# Sheet.net
KiCad netlist of a schematic drawn in Altium Designer
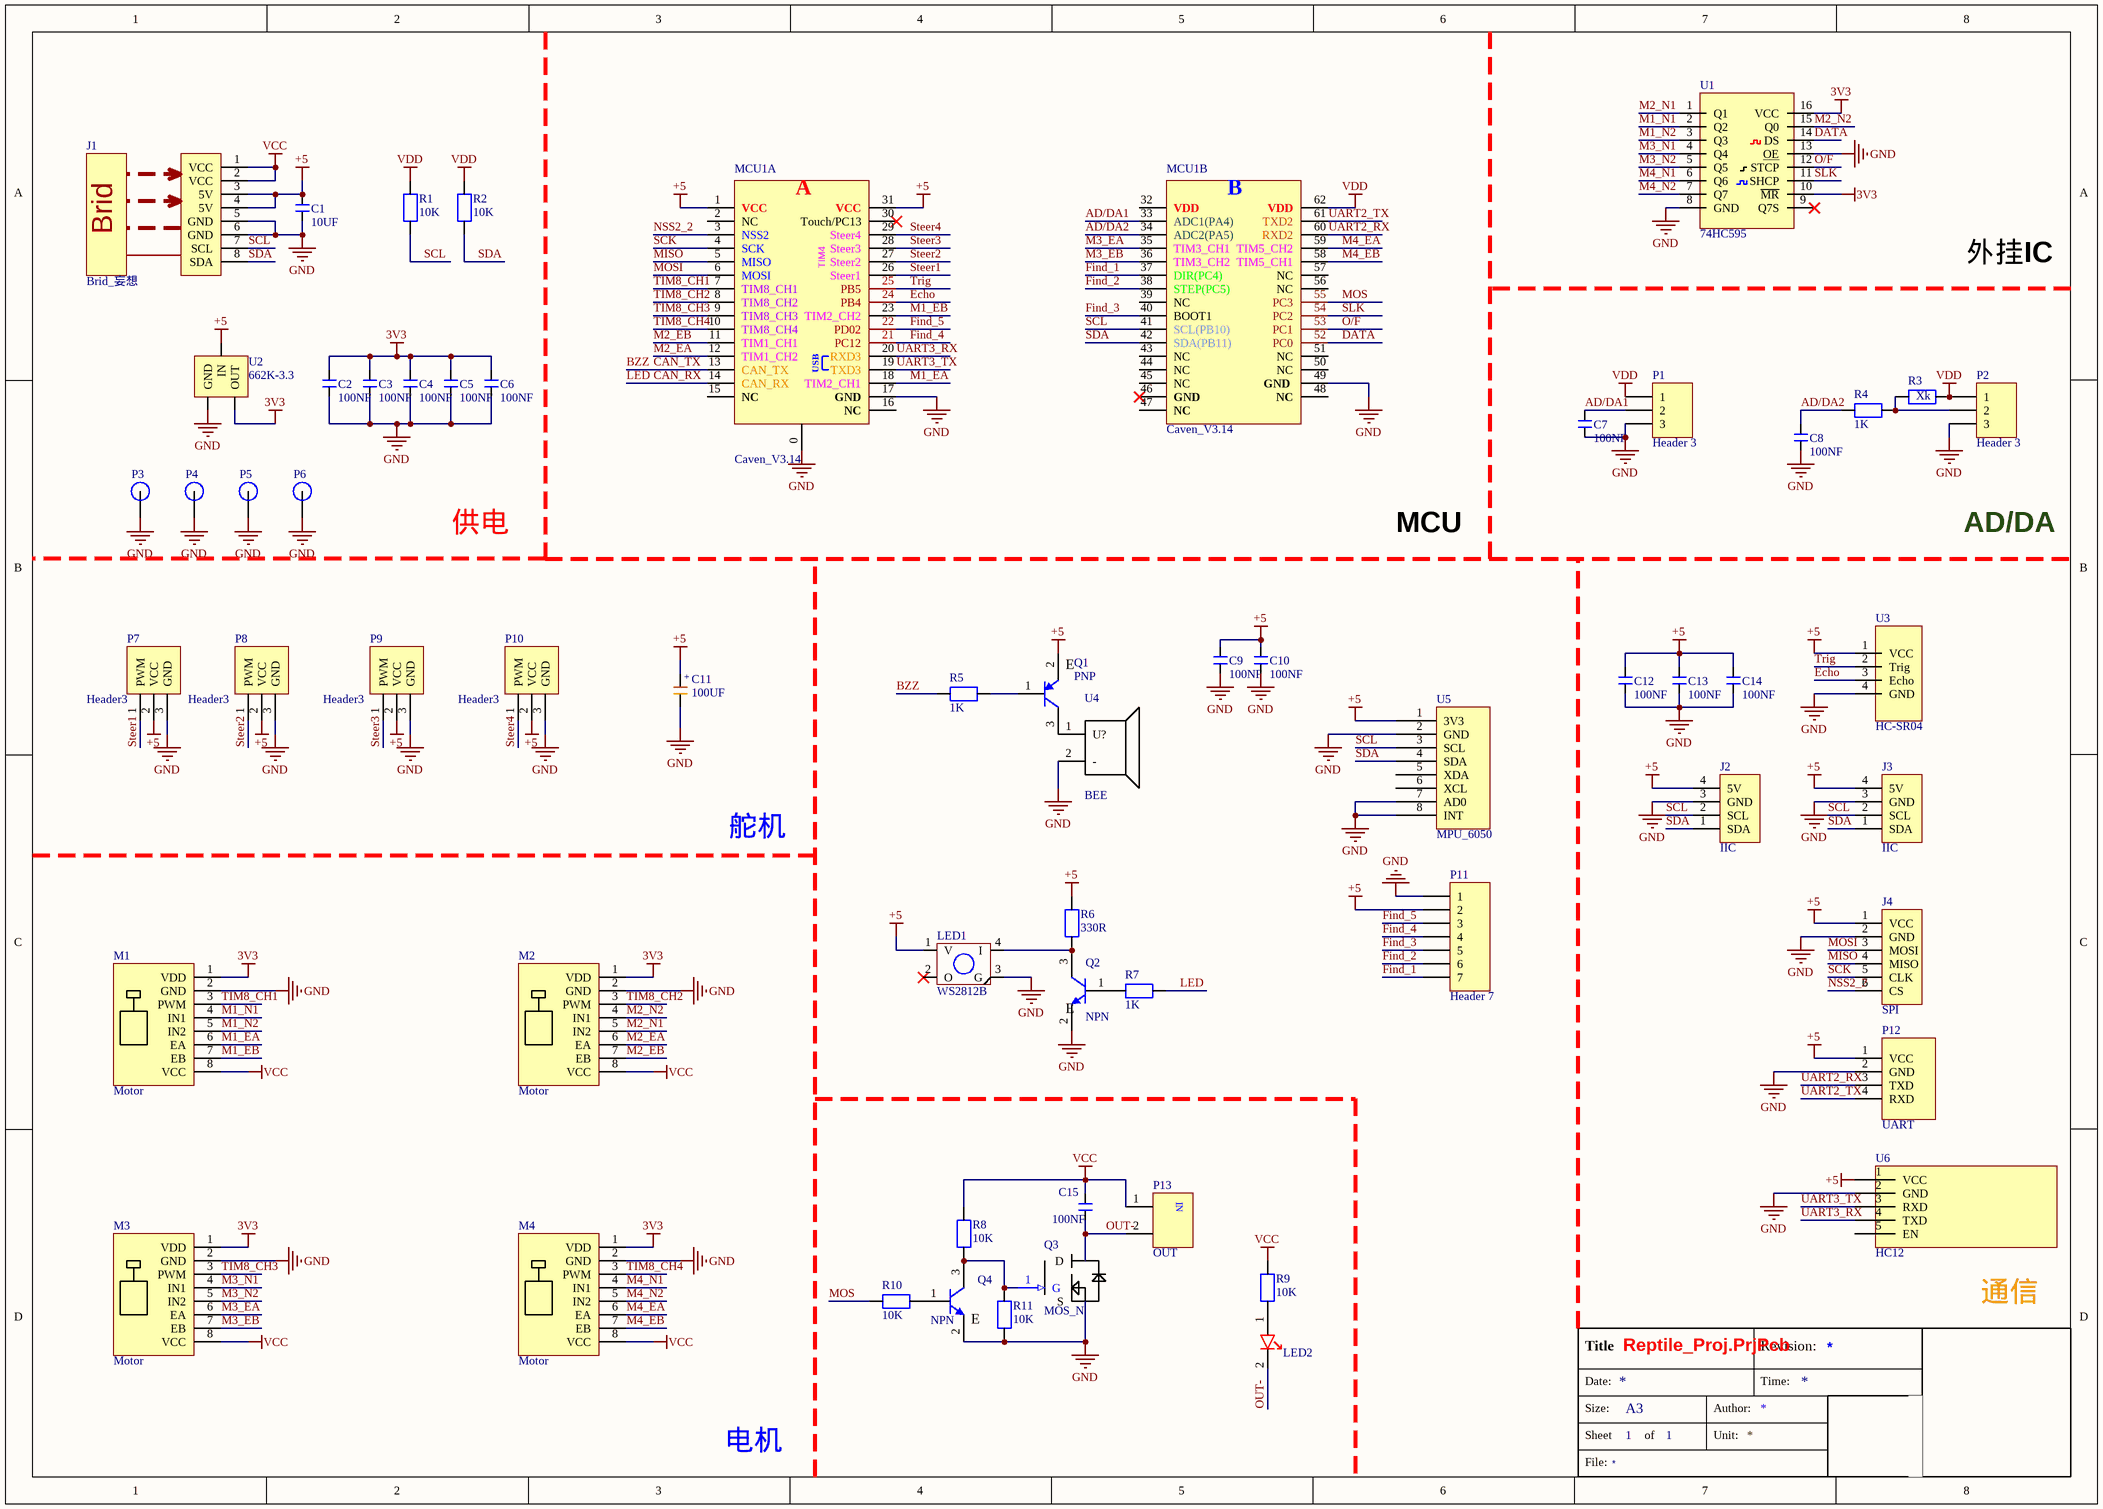
[diagram p0: Sheet.SchDoc]

(export (version "E")
  (design (tool "Eeschema 10.0.6"))
  (components
    (comp (ref "C1")
      (value "10UF")
      (footprint "CAP_1206")
      (description "CAP  12~50V")
      (libsource (lib "User") (part "CAP"))
    )
    (comp (ref "C2")
      (value "100NF")
      (footprint "CAP_0603")
      (description "CAP  12~50V")
      (libsource (lib "User") (part "CAP"))
    )
    (comp (ref "C3")
      (value "100NF")
      (footprint "CAP_0603")
      (description "CAP  12~50V")
      (libsource (lib "User") (part "CAP"))
    )
    (comp (ref "C4")
      (value "100NF")
      (footprint "CAP_0603")
      (description "CAP  12~50V")
      (libsource (lib "User") (part "CAP"))
    )
    (comp (ref "C5")
      (value "100NF")
      (footprint "CAP_0603")
      (description "CAP  12~50V")
      (libsource (lib "User") (part "CAP"))
    )
    (comp (ref "C6")
      (value "100NF")
      (footprint "CAP_0603")
      (description "CAP  12~50V")
      (libsource (lib "User") (part "CAP"))
    )
    (comp (ref "C7")
      (value "100NF")
      (footprint "CAP_0603")
      (description "CAP  12~50V")
      (libsource (lib "User") (part "CAP"))
    )
    (comp (ref "C8")
      (value "100NF")
      (footprint "CAP_0603")
      (description "CAP  12~50V")
      (libsource (lib "User") (part "CAP"))
    )
    (comp (ref "C9")
      (value "100NF")
      (footprint "CAP_0603")
      (description "CAP  12~50V")
      (libsource (lib "User") (part "CAP"))
    )
    (comp (ref "C10")
      (value "100NF")
      (footprint "CAP_0603")
      (description "CAP  12~50V")
      (libsource (lib "User") (part "CAP"))
    )
    (comp (ref "C11")
      (value "100UF")
      (footprint "CAP_3528_B")
      (description "CAP  6~12V  钽电容")
      (libsource (lib "User") (part "CAP_TA"))
    )
    (comp (ref "C12")
      (value "100NF")
      (footprint "CAP_0603")
      (description "CAP  12~50V")
      (libsource (lib "User") (part "CAP"))
    )
    (comp (ref "C13")
      (value "100NF")
      (footprint "CAP_0603")
      (description "CAP  12~50V")
      (libsource (lib "User") (part "CAP"))
    )
    (comp (ref "C14")
      (value "100NF")
      (footprint "CAP_0603")
      (description "CAP  12~50V")
      (libsource (lib "User") (part "CAP"))
    )
    (comp (ref "C15")
      (value "100NF")
      (footprint "CAP_0603")
      (description "CAP  12~50V")
      (libsource (lib "User") (part "CAP"))
    )
    (comp (ref "J1")
      (value "Brid_妄想")
      (footprint "Brid")
      (description "Brid")
      (libsource (lib "User") (part "Brid"))
    )
    (comp (ref "J2")
      (value "IIC")
      (footprint "XH_2.54_4P")
      (description "Heard")
      (libsource (lib "User") (part "IIC"))
    )
    (comp (ref "J3")
      (value "IIC")
      (footprint "IIC-XH2.54-4PIN")
      (description "Heard")
      (libsource (lib "User") (part "IIC"))
    )
    (comp (ref "J4")
      (value "SPI")
      (footprint "Header 2.54X6")
      (description "Heard")
      (libsource (lib "User") (part "SPI"))
    )
    (comp (ref "LED1")
      (value "WS2812B")
      (footprint "5050-RGB")
      (description "LED")
      (libsource (lib "User") (part "WS2812B"))
    )
    (comp (ref "LED2")
      (value "LED_R/G/B/Y")
      (footprint "LED_5MM")
      (description "LED")
      (libsource (lib "User") (part "LED"))
    )
    (comp (ref "M1")
      (value "Motor")
      (footprint "PH_2.0_8P")
      (description "Motor-Brushed-port,XH-1.25mm")
      (libsource (lib "User") (part "Motor-Brushed-port"))
    )
    (comp (ref "M2")
      (value "Motor")
      (footprint "PH_2.0_8P")
      (description "Motor-Brushed-port,XH-1.25mm")
      (libsource (lib "User") (part "Motor-Brushed-port"))
    )
    (comp (ref "M3")
      (value "Motor")
      (footprint "PH_2.0_8P")
      (description "Motor-Brushed-port,XH-1.25mm")
      (libsource (lib "User") (part "Motor-Brushed-port"))
    )
    (comp (ref "M4")
      (value "Motor")
      (footprint "PH_2.0_8P")
      (description "Motor-Brushed-port,XH-1.25mm")
      (libsource (lib "User") (part "Motor-Brushed-port"))
    )
    (comp (ref "MCU1")
      (value "Caven_V3.14")
      (footprint "Caven_3.14")
      (description "MCU_STM32F103RE")
      (libsource (lib "User") (part "Caven_V3.14"))
    )
    (comp (ref "P1")
      (value "Header 3")
      (footprint "Header 2.54X3")
      (description "Header, 3-Pin")
      (fields (field (name "PUBLISHER") "Altium Limited"))
      (libsource (lib "Miscellaneous Connectors") (part "Header 3"))
    )
    (comp (ref "P2")
      (value "Header 3")
      (footprint "Header 2.54X3")
      (description "Header, 3-Pin")
      (fields (field (name "PUBLISHER") "Altium Limited"))
      (libsource (lib "Miscellaneous Connectors") (part "Header 3"))
    )
    (comp (ref "P3")
      (value "铜柱6m")
      (footprint "M3x6_L-Type")
      (description "IN-OUT")
      (libsource (lib "User") (part "Pillar"))
    )
    (comp (ref "P4")
      (value "铜柱6m")
      (footprint "M3x6_L-Type")
      (description "IN-OUT")
      (libsource (lib "User") (part "Pillar"))
    )
    (comp (ref "P5")
      (value "铜柱6m")
      (footprint "M3x6_L-Type")
      (description "IN-OUT")
      (libsource (lib "User") (part "Pillar"))
    )
    (comp (ref "P6")
      (value "铜柱6m")
      (footprint "M3x6_L-Type")
      (description "IN-OUT")
      (libsource (lib "User") (part "Pillar"))
    )
    (comp (ref "P7")
      (value "Header3")
      (footprint "PWM_Steer-F")
      (description "Header")
      (libsource (lib "User") (part "PWM_D"))
    )
    (comp (ref "P8")
      (value "Header3")
      (footprint "PWM_Steer-B")
      (description "Header")
      (libsource (lib "User") (part "PWM_D"))
    )
    (comp (ref "P9")
      (value "Header3")
      (footprint "PWM_Steer-F")
      (description "Header")
      (libsource (lib "User") (part "PWM_D"))
    )
    (comp (ref "P10")
      (value "Header3")
      (footprint "PWM_Steer-B")
      (description "Header")
      (libsource (lib "User") (part "PWM_D"))
    )
    (comp (ref "P11")
      (value "Header 7")
      (footprint "XH2.54-WI-7P")
      (description "Header, 7-Pin")
      (fields (field (name "PUBLISHER") "Altium Limited"))
      (libsource (lib "Miscellaneous Connectors") (part "Header 7"))
    )
    (comp (ref "P12")
      (value "UART")
      (footprint "UART")
      (description "Header")
      (libsource (lib "User") (part "UART"))
    )
    (comp (ref "P13")
      (value "OUT")
      (footprint "PIN-2_5.08")
      (description "Header")
      (libsource (lib "User") (part "IN _2PIN"))
    )
    (comp (ref "Q1") (value "PNP") (footprint "SOT23_3") (libsource (lib "User") (part "PNP")))
    (comp (ref "Q2") (value "NPN") (footprint "SOT23_3") (libsource (lib "User") (part "NPN")))
    (comp (ref "Q3")
      (value "MOS_N")
      (footprint "TO252_2")
      (description "MOS")
      (libsource (lib "User") (part "MOSFET_N"))
    )
    (comp (ref "Q4") (value "NPN") (footprint "SOT23_3") (libsource (lib "User") (part "NPN")))
    (comp (ref "R1")
      (value "10K")
      (footprint "RESC_0603_2")
      (description "RES 贴片")
      (libsource (lib "User") (part "RES"))
    )
    (comp (ref "R2")
      (value "10K")
      (footprint "RESC_0603_2")
      (description "RES 贴片")
      (libsource (lib "User") (part "RES"))
    )
    (comp (ref "R3")
      (value "Xk")
      (footprint "RESC_0603_2")
      (description "RES 贴片")
      (libsource (lib "User") (part "RES"))
    )
    (comp (ref "R4")
      (value "1K")
      (footprint "RESC_0603_2")
      (description "RES 贴片")
      (libsource (lib "User") (part "RES"))
    )
    (comp (ref "R5")
      (value "1K")
      (footprint "RESC_0603_2")
      (description "RES 贴片")
      (libsource (lib "User") (part "RES"))
    )
    (comp (ref "R6")
      (value "330R")
      (footprint "RESC_0603_2")
      (description "RES 贴片")
      (libsource (lib "User") (part "RES"))
    )
    (comp (ref "R7")
      (value "1K")
      (footprint "RESC_0603_2")
      (description "RES 贴片")
      (libsource (lib "User") (part "RES"))
    )
    (comp (ref "R8")
      (value "10K")
      (footprint "RESC_0603_2")
      (description "RES 贴片")
      (libsource (lib "User") (part "RES"))
    )
    (comp (ref "R9")
      (value "10K")
      (footprint "RESC_0603_2")
      (description "RES 贴片")
      (libsource (lib "User") (part "RES"))
    )
    (comp (ref "R10")
      (value "10K")
      (footprint "RESC_0603_2")
      (description "RES 贴片")
      (libsource (lib "User") (part "RES"))
    )
    (comp (ref "R11")
      (value "10K")
      (footprint "RESC_0603_2")
      (description "RES 贴片")
      (libsource (lib "User") (part "RES"))
    )
    (comp (ref "U1")
      (value "74HC595")
      (footprint "SOIC_16")
      (description "IC")
      (libsource (lib "User") (part "74HC595"))
    )
    (comp (ref "U2")
      (value "662K-3.3")
      (footprint "SOT23_3")
      (description "DC-DC")
      (libsource (lib "User") (part "662K"))
    )
    (comp (ref "U3")
      (value "HC-SR04")
      (footprint "Ultrasonic")
      (description "Mode")
      (libsource (lib "User") (part "Ultrasonic"))
    )
    (comp (ref "U4") (value "BEE") (footprint "BEE-FMQ5mm") (libsource (lib "User") (part "BZZ")))
    (comp (ref "U5")
      (value "MPU_6050")
      (footprint "MPU-G521")
      (description "MODE")
      (libsource (lib "User") (part "MPU_6050"))
    )
    (comp (ref "U6")
      (value "HC12")
      (footprint "Header F 2.54X4")
      (description "MODE")
      (libsource (lib "User") (part "HC-12"))
    )
  )
  (nets
    (net (code "1") (name "+5") (class "Default")
      (node (ref "C1") (pin "1") (pinfunction "0_1") (pintype "passive"))
      (node (ref "C10") (pin "2") (pinfunction "0_2") (pintype "passive"))
      (node (ref "C11") (pin "1") (pinfunction "0_1") (pintype "passive"))
      (node (ref "C12") (pin "2") (pinfunction "0_2") (pintype "passive"))
      (node (ref "C13") (pin "2") (pinfunction "0_2") (pintype "passive"))
      (node (ref "C14") (pin "2") (pinfunction "0_2") (pintype "passive"))
      (node (ref "C9") (pin "2") (pinfunction "0_2") (pintype "passive"))
      (node (ref "J1") (pin "3") (pinfunction "5V_3") (pintype "passive"))
      (node (ref "J1") (pin "4") (pinfunction "5V_4") (pintype "passive"))
      (node (ref "J2") (pin "4") (pinfunction "5V_4") (pintype "passive"))
      (node (ref "J3") (pin "4") (pinfunction "5V_4") (pintype "passive"))
      (node (ref "J4") (pin "1") (pinfunction "VCC_1") (pintype "passive"))
      (node (ref "LED1") (pin "1") (pinfunction "V_1") (pintype "passive"))
      (node (ref "MCU1") (pin "1") (pinfunction "VCC_1") (pintype "passive"))
      (node (ref "MCU1") (pin "31") (pinfunction "VCC_31") (pintype "passive"))
      (node (ref "P10") (pin "2") (pinfunction "VCC_2") (pintype "passive"))
      (node (ref "P11") (pin "2") (pinfunction "2_2") (pintype "passive"))
      (node (ref "P12") (pin "1") (pinfunction "VCC_1") (pintype "passive"))
      (node (ref "P7") (pin "2") (pinfunction "VCC_2") (pintype "passive"))
      (node (ref "P8") (pin "2") (pinfunction "VCC_2") (pintype "passive"))
      (node (ref "P9") (pin "2") (pinfunction "VCC_2") (pintype "passive"))
      (node (ref "Q1") (pin "2") (pinfunction "E_2") (pintype "passive"))
      (node (ref "R6") (pin "1") (pinfunction "1_1") (pintype "passive"))
      (node (ref "U2") (pin "3") (pinfunction "IN_3") (pintype "passive"))
      (node (ref "U3") (pin "1") (pinfunction "VCC_1") (pintype "passive"))
      (node (ref "U5") (pin "1") (pinfunction "3V3_1") (pintype "passive"))
      (node (ref "U6") (pin "1") (pinfunction "VCC_1") (pintype "passive"))
    )
    (net (code "2") (name "/AD{slash}DA1") (class "Default")
      (node (ref "C7") (pin "2") (pinfunction "0_2") (pintype "passive"))
      (node (ref "MCU1") (pin "33") (pinfunction "ADC1(PA4)_33") (pintype "passive"))
      (node (ref "P1") (pin "2") (pinfunction "2_2") (pintype "passive"))
    )
    (net (code "3") (name "/AD{slash}DA2") (class "Default")
      (node (ref "C8") (pin "2") (pinfunction "0_2") (pintype "passive"))
      (node (ref "MCU1") (pin "34") (pinfunction "ADC2(PA5)_34") (pintype "passive"))
      (node (ref "R4") (pin "2") (pinfunction "2_2") (pintype "passive"))
    )
    (net (code "4") (name "/BZZ") (class "Default")
      (node (ref "MCU1") (pin "13") (pinfunction "CAN_TX_13") (pintype "passive"))
      (node (ref "R5") (pin "2") (pinfunction "2_2") (pintype "passive"))
    )
    (net (code "5") (name "/CAN_RX") (class "Default")
      (node (ref "MCU1") (pin "14") (pinfunction "CAN_RX_14") (pintype "passive"))
      (node (ref "R7") (pin "1") (pinfunction "1_1") (pintype "passive"))
    )
    (net (code "6") (name "/DATA") (class "Default")
      (node (ref "MCU1") (pin "52") (pinfunction "PC0_52") (pintype "passive"))
      (node (ref "U1") (pin "14") (pinfunction "DS_14") (pintype "passive"))
    )
    (net (code "7") (name "/Echo") (class "Default")
      (node (ref "MCU1") (pin "24") (pinfunction "PB4_24") (pintype "passive"))
      (node (ref "U3") (pin "3") (pinfunction "Echo_3") (pintype "passive"))
    )
    (net (code "8") (name "/Find_1") (class "Default")
      (node (ref "MCU1") (pin "37") (pinfunction "DIR(PC4)_37") (pintype "passive"))
      (node (ref "P11") (pin "7") (pinfunction "7_7") (pintype "passive"))
    )
    (net (code "9") (name "/Find_2") (class "Default")
      (node (ref "MCU1") (pin "38") (pinfunction "STEP(PC5)_38") (pintype "passive"))
      (node (ref "P11") (pin "6") (pinfunction "6_6") (pintype "passive"))
    )
    (net (code "10") (name "/Find_3") (class "Default")
      (node (ref "MCU1") (pin "40") (pinfunction "BOOT1_40") (pintype "passive"))
      (node (ref "P11") (pin "5") (pinfunction "5_5") (pintype "passive"))
    )
    (net (code "11") (name "/Find_4") (class "Default")
      (node (ref "MCU1") (pin "21") (pinfunction "PC12_21") (pintype "passive"))
      (node (ref "P11") (pin "4") (pinfunction "4_4") (pintype "passive"))
    )
    (net (code "12") (name "/Find_5") (class "Default")
      (node (ref "MCU1") (pin "22") (pinfunction "PD02_22") (pintype "passive"))
      (node (ref "P11") (pin "3") (pinfunction "3_3") (pintype "passive"))
    )
    (net (code "13") (name "/M1_EA") (class "Default")
      (node (ref "M1") (pin "6") (pinfunction "EA_6") (pintype "passive"))
      (node (ref "MCU1") (pin "18") (pinfunction "TIM2_CH1_18") (pintype "passive"))
    )
    (net (code "14") (name "/M1_EB") (class "Default")
      (node (ref "M1") (pin "7") (pinfunction "EB_7") (pintype "passive"))
      (node (ref "MCU1") (pin "23") (pinfunction "TIM2_CH2_23") (pintype "passive"))
    )
    (net (code "15") (name "/M1_N1") (class "Default")
      (node (ref "M1") (pin "4") (pinfunction "IN1_4") (pintype "passive"))
      (node (ref "U1") (pin "2") (pinfunction "Q2_2") (pintype "passive"))
    )
    (net (code "16") (name "/M1_N2") (class "Default")
      (node (ref "M1") (pin "5") (pinfunction "IN2_5") (pintype "passive"))
      (node (ref "U1") (pin "3") (pinfunction "Q3_3") (pintype "passive"))
    )
    (net (code "17") (name "/M2_EA") (class "Default")
      (node (ref "M2") (pin "6") (pinfunction "EA_6") (pintype "passive"))
      (node (ref "MCU1") (pin "12") (pinfunction "TIM1_CH2_12") (pintype "passive"))
    )
    (net (code "18") (name "/M2_EB") (class "Default")
      (node (ref "M2") (pin "7") (pinfunction "EB_7") (pintype "passive"))
      (node (ref "MCU1") (pin "11") (pinfunction "TIM1_CH1_11") (pintype "passive"))
    )
    (net (code "19") (name "/M2_N1") (class "Default")
      (node (ref "M2") (pin "5") (pinfunction "IN2_5") (pintype "passive"))
      (node (ref "U1") (pin "1") (pinfunction "Q1_1") (pintype "passive"))
    )
    (net (code "20") (name "/M2_N2") (class "Default")
      (node (ref "M2") (pin "4") (pinfunction "IN1_4") (pintype "passive"))
      (node (ref "U1") (pin "15") (pinfunction "Q0_15") (pintype "passive"))
    )
    (net (code "21") (name "/M3_EA") (class "Default")
      (node (ref "M3") (pin "6") (pinfunction "EA_6") (pintype "passive"))
      (node (ref "MCU1") (pin "35") (pinfunction "TIM3_CH1_35") (pintype "passive"))
    )
    (net (code "22") (name "/M3_EB") (class "Default")
      (node (ref "M3") (pin "7") (pinfunction "EB_7") (pintype "passive"))
      (node (ref "MCU1") (pin "36") (pinfunction "TIM3_CH2_36") (pintype "passive"))
    )
    (net (code "23") (name "/M3_N1") (class "Default")
      (node (ref "M3") (pin "4") (pinfunction "IN1_4") (pintype "passive"))
      (node (ref "U1") (pin "4") (pinfunction "Q4_4") (pintype "passive"))
    )
    (net (code "24") (name "/M3_N2") (class "Default")
      (node (ref "M3") (pin "5") (pinfunction "IN2_5") (pintype "passive"))
      (node (ref "U1") (pin "5") (pinfunction "Q5_5") (pintype "passive"))
    )
    (net (code "25") (name "/M4_EA") (class "Default")
      (node (ref "M4") (pin "6") (pinfunction "EA_6") (pintype "passive"))
      (node (ref "MCU1") (pin "59") (pinfunction "TIM5_CH2_59") (pintype "passive"))
    )
    (net (code "26") (name "/M4_EB") (class "Default")
      (node (ref "M4") (pin "7") (pinfunction "EB_7") (pintype "passive"))
      (node (ref "MCU1") (pin "58") (pinfunction "TIM5_CH1_58") (pintype "passive"))
    )
    (net (code "27") (name "/M4_N1") (class "Default")
      (node (ref "M4") (pin "4") (pinfunction "IN1_4") (pintype "passive"))
      (node (ref "U1") (pin "6") (pinfunction "Q6_6") (pintype "passive"))
    )
    (net (code "28") (name "/M4_N2") (class "Default")
      (node (ref "M4") (pin "5") (pinfunction "IN2_5") (pintype "passive"))
      (node (ref "U1") (pin "7") (pinfunction "Q7_7") (pintype "passive"))
    )
    (net (code "29") (name "/MISO") (class "Default")
      (node (ref "J4") (pin "4") (pinfunction "MISO_4") (pintype "passive"))
      (node (ref "MCU1") (pin "5") (pinfunction "MISO_5") (pintype "passive"))
    )
    (net (code "30") (name "/MOS") (class "Default")
      (node (ref "MCU1") (pin "55") (pinfunction "PC3_55") (pintype "passive"))
      (node (ref "R10") (pin "1") (pinfunction "1_1") (pintype "passive"))
    )
    (net (code "31") (name "/MOSI") (class "Default")
      (node (ref "J4") (pin "3") (pinfunction "MOSI_3") (pintype "passive"))
      (node (ref "MCU1") (pin "6") (pinfunction "MOSI_6") (pintype "passive"))
    )
    (net (code "32") (name "/NSS2_2") (class "Default")
      (node (ref "J4") (pin "6") (pinfunction "CS_6") (pintype "passive"))
      (node (ref "MCU1") (pin "3") (pinfunction "NSS2_3") (pintype "passive"))
    )
    (net (code "33") (name "/OUT-") (class "Default")
      (node (ref "C15") (pin "1") (pinfunction "0_1") (pintype "passive"))
      (node (ref "LED2") (pin "2") (pinfunction "-_2") (pintype "passive"))
      (node (ref "P13") (pin "2") (pintype "passive"))
      (node (ref "Q3") (pin "3") (pinfunction "D_3") (pintype "passive"))
    )
    (net (code "34") (name "/O{slash}F") (class "Default")
      (node (ref "MCU1") (pin "53") (pinfunction "PC1_53") (pintype "passive"))
      (node (ref "U1") (pin "12") (pinfunction "STCP_12") (pintype "passive"))
    )
    (net (code "35") (name "/SCK") (class "Default")
      (node (ref "J4") (pin "5") (pinfunction "CLK_5") (pintype "passive"))
      (node (ref "MCU1") (pin "4") (pinfunction "SCK_4") (pintype "passive"))
    )
    (net (code "36") (name "/SCL") (class "Default")
      (node (ref "J1") (pin "7") (pinfunction "SCL_7") (pintype "passive"))
      (node (ref "J2") (pin "2") (pinfunction "SCL_2") (pintype "passive"))
      (node (ref "J3") (pin "2") (pinfunction "SCL_2") (pintype "passive"))
      (node (ref "MCU1") (pin "41") (pinfunction "SCL(PB10)_41") (pintype "passive"))
      (node (ref "R1") (pin "2") (pinfunction "2_2") (pintype "passive"))
      (node (ref "U5") (pin "3") (pinfunction "SCL_3") (pintype "passive"))
    )
    (net (code "37") (name "/SDA") (class "Default")
      (node (ref "J1") (pin "8") (pinfunction "SDA_8") (pintype "passive"))
      (node (ref "J2") (pin "1") (pinfunction "SDA_1") (pintype "passive"))
      (node (ref "J3") (pin "1") (pinfunction "SDA_1") (pintype "passive"))
      (node (ref "MCU1") (pin "42") (pinfunction "SDA(PB11)_42") (pintype "passive"))
      (node (ref "R2") (pin "2") (pinfunction "2_2") (pintype "passive"))
      (node (ref "U5") (pin "4") (pinfunction "SDA_4") (pintype "passive"))
    )
    (net (code "38") (name "/SLK") (class "Default")
      (node (ref "MCU1") (pin "54") (pinfunction "PC2_54") (pintype "passive"))
      (node (ref "U1") (pin "11") (pinfunction "SHCP_11") (pintype "passive"))
    )
    (net (code "39") (name "/Steer1") (class "Default")
      (node (ref "MCU1") (pin "26") (pinfunction "Steer1_26") (pintype "passive"))
      (node (ref "P7") (pin "1") (pinfunction "PWM_1") (pintype "passive"))
    )
    (net (code "40") (name "/Steer2") (class "Default")
      (node (ref "MCU1") (pin "27") (pinfunction "Steer2_27") (pintype "passive"))
      (node (ref "P8") (pin "1") (pinfunction "PWM_1") (pintype "passive"))
    )
    (net (code "41") (name "/Steer3") (class "Default")
      (node (ref "MCU1") (pin "28") (pinfunction "Steer3_28") (pintype "passive"))
      (node (ref "P9") (pin "1") (pinfunction "PWM_1") (pintype "passive"))
    )
    (net (code "42") (name "/Steer4") (class "Default")
      (node (ref "MCU1") (pin "29") (pinfunction "Steer4_29") (pintype "passive"))
      (node (ref "P10") (pin "1") (pinfunction "PWM_1") (pintype "passive"))
    )
    (net (code "43") (name "/TIM8_CH1") (class "Default")
      (node (ref "M1") (pin "3") (pinfunction "PWM_3") (pintype "passive"))
      (node (ref "MCU1") (pin "7") (pinfunction "TIM8_CH1_7") (pintype "passive"))
    )
    (net (code "44") (name "/TIM8_CH2") (class "Default")
      (node (ref "M2") (pin "3") (pinfunction "PWM_3") (pintype "passive"))
      (node (ref "MCU1") (pin "8") (pinfunction "TIM8_CH2_8") (pintype "passive"))
    )
    (net (code "45") (name "/TIM8_CH3") (class "Default")
      (node (ref "M3") (pin "3") (pinfunction "PWM_3") (pintype "passive"))
      (node (ref "MCU1") (pin "9") (pinfunction "TIM8_CH3_9") (pintype "passive"))
    )
    (net (code "46") (name "/TIM8_CH4") (class "Default")
      (node (ref "M4") (pin "3") (pinfunction "PWM_3") (pintype "passive"))
      (node (ref "MCU1") (pin "10") (pinfunction "TIM8_CH4_10") (pintype "passive"))
    )
    (net (code "47") (name "/Trig") (class "Default")
      (node (ref "MCU1") (pin "25") (pinfunction "PB5_25") (pintype "passive"))
      (node (ref "U3") (pin "2") (pinfunction "Trig_2") (pintype "passive"))
    )
    (net (code "48") (name "/UART2_RX") (class "Default")
      (node (ref "MCU1") (pin "60") (pinfunction "RXD2_60") (pintype "passive"))
      (node (ref "P12") (pin "3") (pinfunction "TXD_3") (pintype "passive"))
    )
    (net (code "49") (name "/UART2_TX") (class "Default")
      (node (ref "MCU1") (pin "61") (pinfunction "TXD2_61") (pintype "passive"))
      (node (ref "P12") (pin "4") (pinfunction "RXD_4") (pintype "passive"))
    )
    (net (code "50") (name "/UART3_RX") (class "Default")
      (node (ref "MCU1") (pin "20") (pinfunction "RXD3_20") (pintype "passive"))
      (node (ref "U6") (pin "4") (pinfunction "TXD_4") (pintype "passive"))
    )
    (net (code "51") (name "/UART3_TX") (class "Default")
      (node (ref "MCU1") (pin "19") (pinfunction "TXD3_19") (pintype "passive"))
      (node (ref "U6") (pin "3") (pinfunction "RXD_3") (pintype "passive"))
    )
    (net (code "52") (name "3V3") (class "Default")
      (node (ref "C2") (pin "1") (pinfunction "0_1") (pintype "passive"))
      (node (ref "C3") (pin "1") (pinfunction "0_1") (pintype "passive"))
      (node (ref "C4") (pin "1") (pinfunction "0_1") (pintype "passive"))
      (node (ref "C5") (pin "1") (pinfunction "0_1") (pintype "passive"))
      (node (ref "C6") (pin "1") (pinfunction "0_1") (pintype "passive"))
      (node (ref "M1") (pin "1") (pinfunction "VDD_1") (pintype "passive"))
      (node (ref "M2") (pin "1") (pinfunction "VDD_1") (pintype "passive"))
      (node (ref "M3") (pin "1") (pinfunction "VDD_1") (pintype "passive"))
      (node (ref "M4") (pin "1") (pinfunction "VDD_1") (pintype "passive"))
      (node (ref "U1") (pin "10") (pinfunction "~{MR}_10") (pintype "passive"))
      (node (ref "U1") (pin "16") (pinfunction "VCC_16") (pintype "passive"))
      (node (ref "U2") (pin "2") (pinfunction "OUT_2") (pintype "passive"))
    )
    (net (code "53") (name "GND") (class "Default")
      (node (ref "C1") (pin "2") (pinfunction "0_2") (pintype "passive"))
      (node (ref "C10") (pin "1") (pinfunction "0_1") (pintype "passive"))
      (node (ref "C11") (pin "2") (pinfunction "0_2") (pintype "passive"))
      (node (ref "C12") (pin "1") (pinfunction "0_1") (pintype "passive"))
      (node (ref "C13") (pin "1") (pinfunction "0_1") (pintype "passive"))
      (node (ref "C14") (pin "1") (pinfunction "0_1") (pintype "passive"))
      (node (ref "C2") (pin "2") (pinfunction "0_2") (pintype "passive"))
      (node (ref "C3") (pin "2") (pinfunction "0_2") (pintype "passive"))
      (node (ref "C4") (pin "2") (pinfunction "0_2") (pintype "passive"))
      (node (ref "C5") (pin "2") (pinfunction "0_2") (pintype "passive"))
      (node (ref "C6") (pin "2") (pinfunction "0_2") (pintype "passive"))
      (node (ref "C7") (pin "1") (pinfunction "0_1") (pintype "passive"))
      (node (ref "C8") (pin "1") (pinfunction "0_1") (pintype "passive"))
      (node (ref "C9") (pin "1") (pinfunction "0_1") (pintype "passive"))
      (node (ref "J1") (pin "5") (pinfunction "GND_5") (pintype "passive"))
      (node (ref "J1") (pin "6") (pinfunction "GND_6") (pintype "passive"))
      (node (ref "J2") (pin "3") (pinfunction "GND_3") (pintype "passive"))
      (node (ref "J3") (pin "3") (pinfunction "GND_3") (pintype "passive"))
      (node (ref "J4") (pin "2") (pinfunction "GND_2") (pintype "passive"))
      (node (ref "LED1") (pin "3") (pinfunction "G_3") (pintype "passive"))
      (node (ref "M1") (pin "2") (pinfunction "GND_2") (pintype "passive"))
      (node (ref "M2") (pin "2") (pinfunction "GND_2") (pintype "passive"))
      (node (ref "M3") (pin "2") (pinfunction "GND_2") (pintype "passive"))
      (node (ref "M4") (pin "2") (pinfunction "GND_2") (pintype "passive"))
      (node (ref "MCU1") (pin "0") (pinfunction "0_0") (pintype "passive"))
      (node (ref "MCU1") (pin "17") (pinfunction "GND_17") (pintype "passive"))
      (node (ref "MCU1") (pin "49") (pinfunction "GND_49") (pintype "passive"))
      (node (ref "P1") (pin "3") (pinfunction "3_3") (pintype "passive"))
      (node (ref "P10") (pin "3") (pinfunction "GND_3") (pintype "passive"))
      (node (ref "P11") (pin "1") (pinfunction "1_1") (pintype "passive"))
      (node (ref "P12") (pin "2") (pinfunction "GND_2") (pintype "passive"))
      (node (ref "P2") (pin "3") (pinfunction "3_3") (pintype "passive"))
      (node (ref "P3") (pin "1") (pinfunction "IO_1") (pintype "passive"))
      (node (ref "P4") (pin "1") (pinfunction "IO_1") (pintype "passive"))
      (node (ref "P5") (pin "1") (pinfunction "IO_1") (pintype "passive"))
      (node (ref "P6") (pin "1") (pinfunction "IO_1") (pintype "passive"))
      (node (ref "P7") (pin "3") (pinfunction "GND_3") (pintype "passive"))
      (node (ref "P8") (pin "3") (pinfunction "GND_3") (pintype "passive"))
      (node (ref "P9") (pin "3") (pinfunction "GND_3") (pintype "passive"))
      (node (ref "Q2") (pin "2") (pinfunction "E_2") (pintype "passive"))
      (node (ref "Q3") (pin "2") (pinfunction "S_2") (pintype "passive"))
      (node (ref "Q4") (pin "2") (pinfunction "E_2") (pintype "passive"))
      (node (ref "R11") (pin "2") (pinfunction "2_2") (pintype "passive"))
      (node (ref "U1") (pin "13") (pinfunction "OE_13") (pintype "passive"))
      (node (ref "U1") (pin "8") (pinfunction "GND_8") (pintype "passive"))
      (node (ref "U2") (pin "1") (pinfunction "GND_1") (pintype "passive"))
      (node (ref "U3") (pin "4") (pinfunction "GND_4") (pintype "passive"))
      (node (ref "U4") (pin "2") (pinfunction "-_2") (pintype "passive"))
      (node (ref "U5") (pin "2") (pinfunction "GND_2") (pintype "passive"))
      (node (ref "U5") (pin "7") (pinfunction "AD0_7") (pintype "passive"))
      (node (ref "U5") (pin "8") (pinfunction "INT_8") (pintype "passive"))
      (node (ref "U6") (pin "2") (pinfunction "GND_2") (pintype "passive"))
    )
    (net (code "54") (name "Net-(LED1-I)") (class "Default")
      (node (ref "LED1") (pin "4") (pinfunction "I_4") (pintype "passive"))
      (node (ref "Q2") (pin "3") (pinfunction "C_3") (pintype "passive"))
      (node (ref "R6") (pin "2") (pinfunction "2_2") (pintype "passive"))
    )
    (net (code "55") (name "Net-(LED2-+)") (class "Default")
      (node (ref "LED2") (pin "1") (pinfunction "+_1") (pintype "passive"))
      (node (ref "R9") (pin "2") (pinfunction "2_2") (pintype "passive"))
    )
    (net (code "56") (name "Net-(P2-Pad2)") (class "Default")
      (node (ref "P2") (pin "2") (pinfunction "2_2") (pintype "passive"))
      (node (ref "R3") (pin "1") (pinfunction "1_1") (pintype "passive"))
      (node (ref "R4") (pin "1") (pinfunction "1_1") (pintype "passive"))
    )
    (net (code "57") (name "Net-(Q1-B)") (class "Default")
      (node (ref "Q1") (pin "1") (pinfunction "B_1") (pintype "passive"))
      (node (ref "R5") (pin "1") (pinfunction "1_1") (pintype "passive"))
    )
    (net (code "58") (name "Net-(Q1-C)") (class "Default")
      (node (ref "Q1") (pin "3") (pinfunction "C_3") (pintype "passive"))
      (node (ref "U4") (pin "1") (pinfunction "U?_1") (pintype "passive"))
    )
    (net (code "59") (name "Net-(Q2-B)") (class "Default")
      (node (ref "Q2") (pin "1") (pinfunction "B_1") (pintype "passive"))
      (node (ref "R7") (pin "2") (pinfunction "2_2") (pintype "passive"))
    )
    (net (code "60") (name "Net-(Q3-G)") (class "Default")
      (node (ref "Q3") (pin "1") (pinfunction "G_1") (pintype "input"))
      (node (ref "Q4") (pin "3") (pinfunction "C_3") (pintype "passive"))
      (node (ref "R11") (pin "1") (pinfunction "1_1") (pintype "passive"))
      (node (ref "R8") (pin "2") (pinfunction "2_2") (pintype "passive"))
    )
    (net (code "61") (name "Net-(Q4-B)") (class "Default")
      (node (ref "Q4") (pin "1") (pinfunction "B_1") (pintype "passive"))
      (node (ref "R10") (pin "2") (pinfunction "2_2") (pintype "passive"))
    )
    (net (code "62") (name "VCC") (class "Default")
      (node (ref "C15") (pin "2") (pinfunction "0_2") (pintype "passive"))
      (node (ref "J1") (pin "1") (pinfunction "VCC_1") (pintype "passive"))
      (node (ref "J1") (pin "2") (pinfunction "VCC_2") (pintype "passive"))
      (node (ref "M1") (pin "8") (pinfunction "VCC_8") (pintype "passive"))
      (node (ref "M2") (pin "8") (pinfunction "VCC_8") (pintype "passive"))
      (node (ref "M3") (pin "8") (pinfunction "VCC_8") (pintype "passive"))
      (node (ref "M4") (pin "8") (pinfunction "VCC_8") (pintype "passive"))
      (node (ref "P13") (pin "1") (pintype "passive"))
      (node (ref "R8") (pin "1") (pinfunction "1_1") (pintype "passive"))
      (node (ref "R9") (pin "1") (pinfunction "1_1") (pintype "passive"))
    )
    (net (code "63") (name "VDD") (class "Default")
      (node (ref "MCU1") (pin "62") (pinfunction "VDD_62") (pintype "passive"))
      (node (ref "P1") (pin "1") (pinfunction "1_1") (pintype "passive"))
      (node (ref "P2") (pin "1") (pinfunction "1_1") (pintype "passive"))
      (node (ref "R1") (pin "1") (pinfunction "1_1") (pintype "passive"))
      (node (ref "R2") (pin "1") (pinfunction "1_1") (pintype "passive"))
      (node (ref "R3") (pin "2") (pinfunction "2_2") (pintype "passive"))
    )
    (net (code "64") (name "unconnected-(LED1-O-Pad2)") (class "Default")
      (node (ref "LED1") (pin "2") (pinfunction "O_2") (pintype "passive+no_connect"))
    )
    (net (code "65") (name "unconnected-(MCU1A-NC-Pad2)") (class "Default")
      (node (ref "MCU1") (pin "2") (pinfunction "NC_2") (pintype "passive"))
    )
    (net (code "66") (name "unconnected-(MCU1A-NC-Pad15)") (class "Default")
      (node (ref "MCU1") (pin "15") (pinfunction "NC_15") (pintype "passive"))
    )
    (net (code "67") (name "unconnected-(MCU1A-NC-Pad16)") (class "Default")
      (node (ref "MCU1") (pin "16") (pinfunction "NC_16") (pintype "passive"))
    )
    (net (code "68") (name "unconnected-(MCU1A-Touch{slash}PC13-Pad30)") (class "Default")
      (node (ref "MCU1") (pin "30") (pinfunction "Touch/PC13_30") (pintype "passive+no_connect"))
    )
    (net (code "69") (name "unconnected-(MCU1B-GND-Pad46)") (class "Default")
      (node (ref "MCU1") (pin "46") (pinfunction "GND_46") (pintype "passive+no_connect"))
    )
    (net (code "70") (name "unconnected-(MCU1B-NC-Pad39)") (class "Default")
      (node (ref "MCU1") (pin "39") (pinfunction "NC_39") (pintype "passive"))
    )
    (net (code "71") (name "unconnected-(MCU1B-NC-Pad43)") (class "Default")
      (node (ref "MCU1") (pin "43") (pinfunction "NC_43") (pintype "passive"))
    )
    (net (code "72") (name "unconnected-(MCU1B-NC-Pad44)") (class "Default")
      (node (ref "MCU1") (pin "44") (pinfunction "NC_44") (pintype "passive"))
    )
    (net (code "73") (name "unconnected-(MCU1B-NC-Pad45)") (class "Default")
      (node (ref "MCU1") (pin "45") (pinfunction "NC_45") (pintype "passive"))
    )
    (net (code "74") (name "unconnected-(MCU1B-NC-Pad47)") (class "Default")
      (node (ref "MCU1") (pin "47") (pinfunction "NC_47") (pintype "passive"))
    )
    (net (code "75") (name "unconnected-(MCU1B-NC-Pad48)") (class "Default")
      (node (ref "MCU1") (pin "48") (pinfunction "NC_48") (pintype "passive"))
    )
    (net (code "76") (name "unconnected-(MCU1B-NC-Pad50)") (class "Default")
      (node (ref "MCU1") (pin "50") (pinfunction "NC_50") (pintype "passive"))
    )
    (net (code "77") (name "unconnected-(MCU1B-NC-Pad51)") (class "Default")
      (node (ref "MCU1") (pin "51") (pinfunction "NC_51") (pintype "passive"))
    )
    (net (code "78") (name "unconnected-(MCU1B-NC-Pad56)") (class "Default")
      (node (ref "MCU1") (pin "56") (pinfunction "NC_56") (pintype "passive"))
    )
    (net (code "79") (name "unconnected-(MCU1B-NC-Pad57)") (class "Default")
      (node (ref "MCU1") (pin "57") (pinfunction "NC_57") (pintype "passive"))
    )
    (net (code "80") (name "unconnected-(MCU1B-VDD-Pad32)") (class "Default")
      (node (ref "MCU1") (pin "32") (pinfunction "VDD_32") (pintype "passive"))
    )
    (net (code "81") (name "unconnected-(U1-Q7S-Pad9)") (class "Default")
      (node (ref "U1") (pin "9") (pinfunction "Q7S_9") (pintype "passive+no_connect"))
    )
    (net (code "82") (name "unconnected-(U5-XCL-Pad6)") (class "Default")
      (node (ref "U5") (pin "6") (pinfunction "XCL_6") (pintype "passive"))
    )
    (net (code "83") (name "unconnected-(U5-XDA-Pad5)") (class "Default")
      (node (ref "U5") (pin "5") (pinfunction "XDA_5") (pintype "passive"))
    )
    (net (code "84") (name "unconnected-(U6-EN-Pad5)") (class "Default")
      (node (ref "U6") (pin "5") (pinfunction "EN_5") (pintype "passive"))
    )
  )
)
